# SparkFun_PWM_Shield.net
KiCad netlist of a schematic drawn in EAGLE
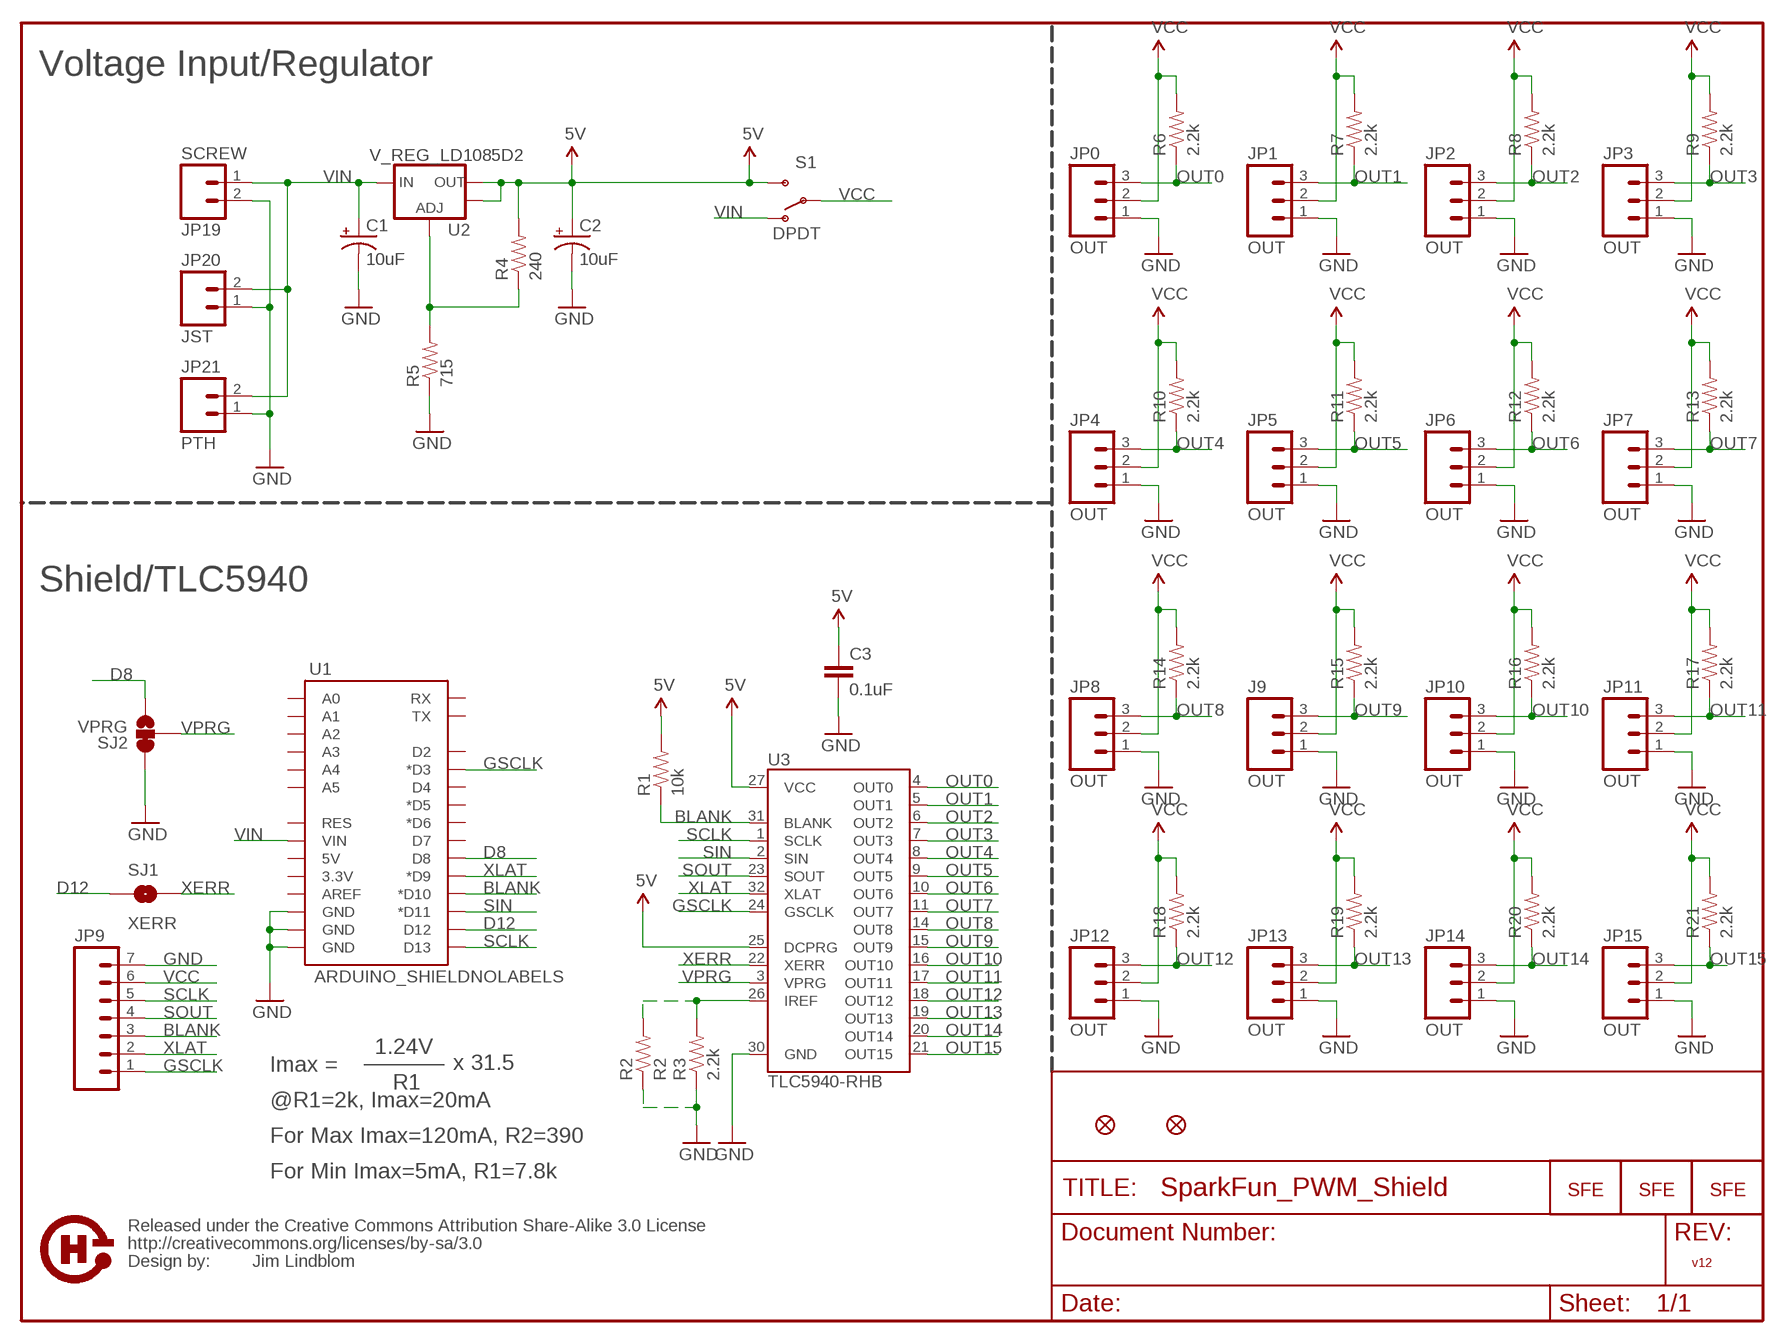
[diagram p0: schematic, sheet 1]

(export (version "E")
  (design (tool "Eeschema 10.0.6"))
  (components
    (comp (ref "C1")
      (value "10uF")
      (footprint "eagle-import:EIA3528")
      (libsource (lib "eagle-import") (part "CAP_POL3528"))
    )
    (comp (ref "C2")
      (value "10uF")
      (footprint "eagle-import:EIA3216")
      (libsource (lib "eagle-import") (part "CAP_POL1206"))
    )
    (comp (ref "C3")
      (value "0.1uF")
      (footprint "eagle-import:0402-CAP")
      (libsource (lib "eagle-import") (part "CAP0402-CAP"))
    )
    (comp (ref "J9")
      (value "OUT")
      (footprint "eagle-import:1X03")
      (libsource (lib "eagle-import") (part "M03PTH"))
    )
    (comp (ref "JP0")
      (value "OUT")
      (footprint "eagle-import:1X03")
      (libsource (lib "eagle-import") (part "M03PTH"))
    )
    (comp (ref "JP1")
      (value "OUT")
      (footprint "eagle-import:1X03")
      (libsource (lib "eagle-import") (part "M03PTH"))
    )
    (comp (ref "JP2")
      (value "OUT")
      (footprint "eagle-import:1X03")
      (libsource (lib "eagle-import") (part "M03PTH"))
    )
    (comp (ref "JP3")
      (value "OUT")
      (footprint "eagle-import:1X03")
      (libsource (lib "eagle-import") (part "M03PTH"))
    )
    (comp (ref "JP4")
      (value "OUT")
      (footprint "eagle-import:1X03")
      (libsource (lib "eagle-import") (part "M03PTH"))
    )
    (comp (ref "JP5")
      (value "OUT")
      (footprint "eagle-import:1X03")
      (libsource (lib "eagle-import") (part "M03PTH"))
    )
    (comp (ref "JP6")
      (value "OUT")
      (footprint "eagle-import:1X03")
      (libsource (lib "eagle-import") (part "M03PTH"))
    )
    (comp (ref "JP7")
      (value "OUT")
      (footprint "eagle-import:1X03")
      (libsource (lib "eagle-import") (part "M03PTH"))
    )
    (comp (ref "JP8")
      (value "OUT")
      (footprint "eagle-import:1X03")
      (libsource (lib "eagle-import") (part "M03PTH"))
    )
    (comp (ref "JP9")
      (value "M07")
      (footprint "eagle-import:1X07")
      (libsource (lib "eagle-import") (part "M07"))
    )
    (comp (ref "JP10")
      (value "OUT")
      (footprint "eagle-import:1X03")
      (libsource (lib "eagle-import") (part "M03PTH"))
    )
    (comp (ref "JP11")
      (value "OUT")
      (footprint "eagle-import:1X03")
      (libsource (lib "eagle-import") (part "M03PTH"))
    )
    (comp (ref "JP12")
      (value "OUT")
      (footprint "eagle-import:1X03")
      (libsource (lib "eagle-import") (part "M03PTH"))
    )
    (comp (ref "JP13")
      (value "OUT")
      (footprint "eagle-import:1X03")
      (libsource (lib "eagle-import") (part "M03PTH"))
    )
    (comp (ref "JP14")
      (value "OUT")
      (footprint "eagle-import:1X03")
      (libsource (lib "eagle-import") (part "M03PTH"))
    )
    (comp (ref "JP15")
      (value "OUT")
      (footprint "eagle-import:1X03")
      (libsource (lib "eagle-import") (part "M03PTH"))
    )
    (comp (ref "JP16")
      (value "LOGO-SFENEW")
      (footprint "eagle-import:SFE-NEW-WEBLOGO")
      (libsource (lib "eagle-import") (part "LOGO-SFENEW"))
    )
    (comp (ref "JP17")
      (value "LOGO-SFESK")
      (footprint "eagle-import:SFE-LOGO-FLAME")
      (libsource (lib "eagle-import") (part "LOGO-SFESK"))
    )
    (comp (ref "JP18")
      (value "LOGO-SFENW2")
      (footprint "eagle-import:SFE-NEW-WEB")
      (libsource (lib "eagle-import") (part "LOGO-SFENW2"))
    )
    (comp (ref "JP19")
      (value "SCREW")
      (footprint "eagle-import:SCREWTERMINAL-3.5MM-2-NS")
      (libsource (lib "eagle-import") (part "M023.5MM-NO_SILK"))
    )
    (comp (ref "JP20")
      (value "JST")
      (footprint "eagle-import:JST-2-PTH")
      (libsource (lib "eagle-import") (part "M02JST-PTH-2"))
    )
    (comp (ref "JP21")
      (value "PTH")
      (footprint "eagle-import:1X02")
      (libsource (lib "eagle-import") (part "M02PTH"))
    )
    (comp (ref "JP22")
      (value "FIDUCIAL1X2")
      (footprint "eagle-import:FIDUCIAL-1X2")
      (libsource (lib "eagle-import") (part "FIDUCIAL1X2"))
    )
    (comp (ref "JP23")
      (value "FIDUCIAL1X2")
      (footprint "eagle-import:FIDUCIAL-1X2")
      (libsource (lib "eagle-import") (part "FIDUCIAL1X2"))
    )
    (comp (ref "R1")
      (value "10k")
      (footprint "eagle-import:0402-RES")
      (libsource (lib "eagle-import") (part "RESISTOR0402-RES"))
    )
    (comp (ref "R2")
      (value "R2")
      (footprint "eagle-import:AXIAL-0.3")
      (libsource (lib "eagle-import") (part "RESISTORAXIAL-0.3"))
    )
    (comp (ref "R3")
      (value "2.2k")
      (footprint "eagle-import:0402-RES")
      (libsource (lib "eagle-import") (part "RESISTOR0402-RES"))
    )
    (comp (ref "R4")
      (value "240")
      (footprint "eagle-import:0402-RES")
      (libsource (lib "eagle-import") (part "RESISTOR0402-RES"))
    )
    (comp (ref "R5")
      (value "715")
      (footprint "eagle-import:0402-RES")
      (libsource (lib "eagle-import") (part "RESISTOR0402-RES"))
    )
    (comp (ref "R6")
      (value "2.2k")
      (footprint "eagle-import:0402-RES")
      (libsource (lib "eagle-import") (part "RESISTOR0402-RES"))
    )
    (comp (ref "R7")
      (value "2.2k")
      (footprint "eagle-import:0402-RES")
      (libsource (lib "eagle-import") (part "RESISTOR0402-RES"))
    )
    (comp (ref "R8")
      (value "2.2k")
      (footprint "eagle-import:0402-RES")
      (libsource (lib "eagle-import") (part "RESISTOR0402-RES"))
    )
    (comp (ref "R9")
      (value "2.2k")
      (footprint "eagle-import:0402-RES")
      (libsource (lib "eagle-import") (part "RESISTOR0402-RES"))
    )
    (comp (ref "R10")
      (value "2.2k")
      (footprint "eagle-import:0402-RES")
      (libsource (lib "eagle-import") (part "RESISTOR0402-RES"))
    )
    (comp (ref "R11")
      (value "2.2k")
      (footprint "eagle-import:0402-RES")
      (libsource (lib "eagle-import") (part "RESISTOR0402-RES"))
    )
    (comp (ref "R12")
      (value "2.2k")
      (footprint "eagle-import:0402-RES")
      (libsource (lib "eagle-import") (part "RESISTOR0402-RES"))
    )
    (comp (ref "R13")
      (value "2.2k")
      (footprint "eagle-import:0402-RES")
      (libsource (lib "eagle-import") (part "RESISTOR0402-RES"))
    )
    (comp (ref "R14")
      (value "2.2k")
      (footprint "eagle-import:0402-RES")
      (libsource (lib "eagle-import") (part "RESISTOR0402-RES"))
    )
    (comp (ref "R15")
      (value "2.2k")
      (footprint "eagle-import:0402-RES")
      (libsource (lib "eagle-import") (part "RESISTOR0402-RES"))
    )
    (comp (ref "R16")
      (value "2.2k")
      (footprint "eagle-import:0402-RES")
      (libsource (lib "eagle-import") (part "RESISTOR0402-RES"))
    )
    (comp (ref "R17")
      (value "2.2k")
      (footprint "eagle-import:0402-RES")
      (libsource (lib "eagle-import") (part "RESISTOR0402-RES"))
    )
    (comp (ref "R18")
      (value "2.2k")
      (footprint "eagle-import:0402-RES")
      (libsource (lib "eagle-import") (part "RESISTOR0402-RES"))
    )
    (comp (ref "R19")
      (value "2.2k")
      (footprint "eagle-import:0402-RES")
      (libsource (lib "eagle-import") (part "RESISTOR0402-RES"))
    )
    (comp (ref "R20")
      (value "2.2k")
      (footprint "eagle-import:0402-RES")
      (libsource (lib "eagle-import") (part "RESISTOR0402-RES"))
    )
    (comp (ref "R21")
      (value "2.2k")
      (footprint "eagle-import:0402-RES")
      (libsource (lib "eagle-import") (part "RESISTOR0402-RES"))
    )
    (comp (ref "S1")
      (value "DPDT")
      (footprint "eagle-import:AYZ0202")
      (libsource (lib "eagle-import") (part "SWITCH-SPSTSMD"))
    )
    (comp (ref "SJ1")
      (value "XERR")
      (footprint "eagle-import:SJ_2S-NO")
      (libsource (lib "eagle-import") (part "SOLDERJUMPERNO"))
    )
    (comp (ref "SJ2")
      (value "VPRG")
      (footprint "eagle-import:SJ_3")
      (libsource (lib "eagle-import") (part "SOLDERJUMPER_2WAYS"))
    )
    (comp (ref "U$1")
      (value "OSHW-LOGOORB")
      (footprint "eagle-import:OSHW-LOGO-GO")
      (libsource (lib "eagle-import") (part "OSHW-LOGOORB"))
    )
    (comp (ref "U$2")
      (value "CREATIVE_COMMONS")
      (footprint "eagle-import:CREATIVE_COMMONS")
      (libsource (lib "eagle-import") (part "CREATIVE_COMMONS"))
    )
    (comp (ref "U1")
      (value "ARDUINO_SHIELDNOLABELS")
      (footprint "eagle-import:DUEMILANOVE_SHIELD_NOLABELS")
      (libsource (lib "eagle-import") (part "ARDUINO_SHIELDNOLABELS"))
    )
    (comp (ref "U2")
      (value "V_REG_LD1085D2")
      (footprint "eagle-import:D2PACK_A")
      (libsource (lib "eagle-import") (part "V_REG_LD1085D2"))
    )
    (comp (ref "U3")
      (value "TLC5940-RHB")
      (footprint "eagle-import:QFN-32")
      (libsource (lib "eagle-import") (part "TLC5940-RHB"))
    )
  )
  (nets
    (net (code "1") (name "/BLANK") (class "Default")
      (node (ref "JP9") (pin "3") (pinfunction "3_3") (pintype "passive"))
      (node (ref "R1") (pin "1") (pinfunction "1_1") (pintype "passive"))
      (node (ref "U1") (pin "D10") (pinfunction "*D10_D10") (pintype "bidirectional"))
      (node (ref "U3") (pin "31") (pinfunction "BLANK_31") (pintype "bidirectional"))
    )
    (net (code "2") (name "/D8") (class "Default")
      (node (ref "SJ2") (pin "3") (pinfunction "3_3") (pintype "passive"))
      (node (ref "U1") (pin "D8") (pinfunction "D8_D8") (pintype "bidirectional"))
    )
    (net (code "3") (name "/D12") (class "Default")
      (node (ref "SJ1") (pin "1") (pinfunction "1_1") (pintype "passive"))
      (node (ref "U1") (pin "D12") (pinfunction "D12_D12") (pintype "bidirectional"))
    )
    (net (code "4") (name "/GSCLK") (class "Default")
      (node (ref "JP9") (pin "1") (pinfunction "1_1") (pintype "passive"))
      (node (ref "U1") (pin "D3") (pinfunction "*D3_D3") (pintype "bidirectional"))
      (node (ref "U3") (pin "24") (pinfunction "GSCLK_24") (pintype "bidirectional"))
    )
    (net (code "5") (name "/OUT0") (class "Default")
      (node (ref "JP0") (pin "3") (pinfunction "3_3") (pintype "passive"))
      (node (ref "R6") (pin "1") (pinfunction "1_1") (pintype "passive"))
      (node (ref "U3") (pin "4") (pinfunction "OUT0_4") (pintype "bidirectional"))
    )
    (net (code "6") (name "/OUT1") (class "Default")
      (node (ref "JP1") (pin "3") (pinfunction "3_3") (pintype "passive"))
      (node (ref "R7") (pin "1") (pinfunction "1_1") (pintype "passive"))
      (node (ref "U3") (pin "5") (pinfunction "OUT1_5") (pintype "bidirectional"))
    )
    (net (code "7") (name "/OUT2") (class "Default")
      (node (ref "JP2") (pin "3") (pinfunction "3_3") (pintype "passive"))
      (node (ref "R8") (pin "1") (pinfunction "1_1") (pintype "passive"))
      (node (ref "U3") (pin "6") (pinfunction "OUT2_6") (pintype "bidirectional"))
    )
    (net (code "8") (name "/OUT3") (class "Default")
      (node (ref "JP3") (pin "3") (pinfunction "3_3") (pintype "passive"))
      (node (ref "R9") (pin "1") (pinfunction "1_1") (pintype "passive"))
      (node (ref "U3") (pin "7") (pinfunction "OUT3_7") (pintype "bidirectional"))
    )
    (net (code "9") (name "/OUT4") (class "Default")
      (node (ref "JP4") (pin "3") (pinfunction "3_3") (pintype "passive"))
      (node (ref "R10") (pin "1") (pinfunction "1_1") (pintype "passive"))
      (node (ref "U3") (pin "8") (pinfunction "OUT4_8") (pintype "bidirectional"))
    )
    (net (code "10") (name "/OUT5") (class "Default")
      (node (ref "JP5") (pin "3") (pinfunction "3_3") (pintype "passive"))
      (node (ref "R11") (pin "1") (pinfunction "1_1") (pintype "passive"))
      (node (ref "U3") (pin "9") (pinfunction "OUT5_9") (pintype "bidirectional"))
    )
    (net (code "11") (name "/OUT6") (class "Default")
      (node (ref "JP6") (pin "3") (pinfunction "3_3") (pintype "passive"))
      (node (ref "R12") (pin "1") (pinfunction "1_1") (pintype "passive"))
      (node (ref "U3") (pin "10") (pinfunction "OUT6_10") (pintype "bidirectional"))
    )
    (net (code "12") (name "/OUT7") (class "Default")
      (node (ref "JP7") (pin "3") (pinfunction "3_3") (pintype "passive"))
      (node (ref "R13") (pin "1") (pinfunction "1_1") (pintype "passive"))
      (node (ref "U3") (pin "11") (pinfunction "OUT7_11") (pintype "bidirectional"))
    )
    (net (code "13") (name "/OUT8") (class "Default")
      (node (ref "JP8") (pin "3") (pinfunction "3_3") (pintype "passive"))
      (node (ref "R14") (pin "1") (pinfunction "1_1") (pintype "passive"))
      (node (ref "U3") (pin "14") (pinfunction "OUT8_14") (pintype "bidirectional"))
    )
    (net (code "14") (name "/OUT9") (class "Default")
      (node (ref "J9") (pin "3") (pinfunction "3_3") (pintype "passive"))
      (node (ref "R15") (pin "1") (pinfunction "1_1") (pintype "passive"))
      (node (ref "U3") (pin "15") (pinfunction "OUT9_15") (pintype "bidirectional"))
    )
    (net (code "15") (name "/OUT10") (class "Default")
      (node (ref "JP10") (pin "3") (pinfunction "3_3") (pintype "passive"))
      (node (ref "R16") (pin "1") (pinfunction "1_1") (pintype "passive"))
      (node (ref "U3") (pin "16") (pinfunction "OUT10_16") (pintype "bidirectional"))
    )
    (net (code "16") (name "/OUT11") (class "Default")
      (node (ref "JP11") (pin "3") (pinfunction "3_3") (pintype "passive"))
      (node (ref "R17") (pin "1") (pinfunction "1_1") (pintype "passive"))
      (node (ref "U3") (pin "17") (pinfunction "OUT11_17") (pintype "bidirectional"))
    )
    (net (code "17") (name "/OUT12") (class "Default")
      (node (ref "JP12") (pin "3") (pinfunction "3_3") (pintype "passive"))
      (node (ref "R18") (pin "1") (pinfunction "1_1") (pintype "passive"))
      (node (ref "U3") (pin "18") (pinfunction "OUT12_18") (pintype "bidirectional"))
    )
    (net (code "18") (name "/OUT13") (class "Default")
      (node (ref "JP13") (pin "3") (pinfunction "3_3") (pintype "passive"))
      (node (ref "R19") (pin "1") (pinfunction "1_1") (pintype "passive"))
      (node (ref "U3") (pin "19") (pinfunction "OUT13_19") (pintype "bidirectional"))
    )
    (net (code "19") (name "/OUT14") (class "Default")
      (node (ref "JP14") (pin "3") (pinfunction "3_3") (pintype "passive"))
      (node (ref "R20") (pin "1") (pinfunction "1_1") (pintype "passive"))
      (node (ref "U3") (pin "20") (pinfunction "OUT14_20") (pintype "bidirectional"))
    )
    (net (code "20") (name "/OUT15") (class "Default")
      (node (ref "JP15") (pin "3") (pinfunction "3_3") (pintype "passive"))
      (node (ref "R21") (pin "1") (pinfunction "1_1") (pintype "passive"))
      (node (ref "U3") (pin "21") (pinfunction "OUT15_21") (pintype "bidirectional"))
    )
    (net (code "21") (name "/SCLK") (class "Default")
      (node (ref "JP9") (pin "5") (pinfunction "5_5") (pintype "passive"))
      (node (ref "U1") (pin "D13") (pinfunction "D13_D13") (pintype "bidirectional"))
      (node (ref "U3") (pin "1") (pinfunction "SCLK_1") (pintype "bidirectional"))
    )
    (net (code "22") (name "/SIN") (class "Default")
      (node (ref "U1") (pin "D11") (pinfunction "*D11_D11") (pintype "bidirectional"))
      (node (ref "U3") (pin "2") (pinfunction "SIN_2") (pintype "bidirectional"))
    )
    (net (code "23") (name "/SOUT") (class "Default")
      (node (ref "JP9") (pin "4") (pinfunction "4_4") (pintype "passive"))
      (node (ref "U3") (pin "23") (pinfunction "SOUT_23") (pintype "bidirectional"))
    )
    (net (code "24") (name "/VIN") (class "Default")
      (node (ref "C1") (pin "A") (pinfunction "+_A") (pintype "passive"))
      (node (ref "JP19") (pin "1") (pinfunction "1_1") (pintype "passive"))
      (node (ref "JP20") (pin "2") (pinfunction "2_2") (pintype "passive"))
      (node (ref "JP21") (pin "2") (pinfunction "2_2") (pintype "passive"))
      (node (ref "S1") (pin "1") (pinfunction "O_1") (pintype "passive"))
      (node (ref "U1") (pin "VIN") (pinfunction "VIN_VIN") (pintype "bidirectional"))
      (node (ref "U2") (pin "3") (pinfunction "IN_3") (pintype "input"))
    )
    (net (code "25") (name "/VPRG") (class "Default")
      (node (ref "SJ2") (pin "2") (pinfunction "2_2") (pintype "passive"))
      (node (ref "U3") (pin "3") (pinfunction "VPRG_3") (pintype "bidirectional"))
    )
    (net (code "26") (name "/XERR") (class "Default")
      (node (ref "SJ1") (pin "2") (pinfunction "2_2") (pintype "passive"))
      (node (ref "U3") (pin "22") (pinfunction "XERR_22") (pintype "bidirectional"))
    )
    (net (code "27") (name "/XLAT") (class "Default")
      (node (ref "JP9") (pin "2") (pinfunction "2_2") (pintype "passive"))
      (node (ref "U1") (pin "D9") (pinfunction "*D9_D9") (pintype "bidirectional"))
      (node (ref "U3") (pin "32") (pinfunction "XLAT_32") (pintype "bidirectional"))
    )
    (net (code "28") (name "5V") (class "Default")
      (node (ref "C2") (pin "A") (pinfunction "+_A") (pintype "passive"))
      (node (ref "C3") (pin "1") (pinfunction "1_1") (pintype "passive"))
      (node (ref "R1") (pin "2") (pinfunction "2_2") (pintype "passive"))
      (node (ref "R4") (pin "2") (pinfunction "2_2") (pintype "passive"))
      (node (ref "S1") (pin "3") (pinfunction "S_3") (pintype "passive"))
      (node (ref "U2") (pin "2") (pinfunction "OUT_2") (pintype "output"))
      (node (ref "U2") (pin "TAB") (pinfunction "OUT_TAB") (pintype "output"))
      (node (ref "U3") (pin "25") (pinfunction "DCPRG_25") (pintype "bidirectional"))
      (node (ref "U3") (pin "27") (pinfunction "VCC_27") (pintype "bidirectional"))
    )
    (net (code "29") (name "GND") (class "Default")
      (node (ref "C1") (pin "C") (pinfunction "-_C") (pintype "passive"))
      (node (ref "C2") (pin "C") (pinfunction "-_C") (pintype "passive"))
      (node (ref "C3") (pin "2") (pinfunction "2_2") (pintype "passive"))
      (node (ref "J9") (pin "1") (pinfunction "1_1") (pintype "passive"))
      (node (ref "JP0") (pin "1") (pinfunction "1_1") (pintype "passive"))
      (node (ref "JP1") (pin "1") (pinfunction "1_1") (pintype "passive"))
      (node (ref "JP10") (pin "1") (pinfunction "1_1") (pintype "passive"))
      (node (ref "JP11") (pin "1") (pinfunction "1_1") (pintype "passive"))
      (node (ref "JP12") (pin "1") (pinfunction "1_1") (pintype "passive"))
      (node (ref "JP13") (pin "1") (pinfunction "1_1") (pintype "passive"))
      (node (ref "JP14") (pin "1") (pinfunction "1_1") (pintype "passive"))
      (node (ref "JP15") (pin "1") (pinfunction "1_1") (pintype "passive"))
      (node (ref "JP19") (pin "2") (pinfunction "2_2") (pintype "passive"))
      (node (ref "JP2") (pin "1") (pinfunction "1_1") (pintype "passive"))
      (node (ref "JP20") (pin "1") (pinfunction "1_1") (pintype "passive"))
      (node (ref "JP21") (pin "1") (pinfunction "1_1") (pintype "passive"))
      (node (ref "JP3") (pin "1") (pinfunction "1_1") (pintype "passive"))
      (node (ref "JP4") (pin "1") (pinfunction "1_1") (pintype "passive"))
      (node (ref "JP5") (pin "1") (pinfunction "1_1") (pintype "passive"))
      (node (ref "JP6") (pin "1") (pinfunction "1_1") (pintype "passive"))
      (node (ref "JP7") (pin "1") (pinfunction "1_1") (pintype "passive"))
      (node (ref "JP8") (pin "1") (pinfunction "1_1") (pintype "passive"))
      (node (ref "JP9") (pin "7") (pinfunction "7_7") (pintype "passive"))
      (node (ref "R2") (pin "P$1") (pinfunction "1_P$1") (pintype "passive"))
      (node (ref "R3") (pin "1") (pinfunction "1_1") (pintype "passive"))
      (node (ref "R5") (pin "1") (pinfunction "1_1") (pintype "passive"))
      (node (ref "SJ2") (pin "1") (pinfunction "1_1") (pintype "passive"))
      (node (ref "U1") (pin "GND@0") (pinfunction "GND_GND@0") (pintype "bidirectional"))
      (node (ref "U1") (pin "GND@1") (pinfunction "GND_GND@1") (pintype "bidirectional"))
      (node (ref "U1") (pin "GND@2") (pinfunction "GND_GND@2") (pintype "bidirectional"))
      (node (ref "U3") (pin "30") (pinfunction "GND_30") (pintype "bidirectional"))
    )
    (net (code "30") (name "Net-(R2-2)") (class "Default")
      (node (ref "R2") (pin "P$2") (pinfunction "2_P$2") (pintype "passive"))
      (node (ref "R3") (pin "2") (pinfunction "2_2") (pintype "passive"))
      (node (ref "U3") (pin "26") (pinfunction "IREF_26") (pintype "bidirectional"))
    )
    (net (code "31") (name "Net-(U2-ADJ)") (class "Default")
      (node (ref "R4") (pin "1") (pinfunction "1_1") (pintype "passive"))
      (node (ref "R5") (pin "2") (pinfunction "2_2") (pintype "passive"))
      (node (ref "U2") (pin "1") (pinfunction "ADJ_1") (pintype "input"))
    )
    (net (code "32") (name "VCC") (class "Default")
      (node (ref "J9") (pin "2") (pinfunction "2_2") (pintype "passive"))
      (node (ref "JP0") (pin "2") (pinfunction "2_2") (pintype "passive"))
      (node (ref "JP1") (pin "2") (pinfunction "2_2") (pintype "passive"))
      (node (ref "JP10") (pin "2") (pinfunction "2_2") (pintype "passive"))
      (node (ref "JP11") (pin "2") (pinfunction "2_2") (pintype "passive"))
      (node (ref "JP12") (pin "2") (pinfunction "2_2") (pintype "passive"))
      (node (ref "JP13") (pin "2") (pinfunction "2_2") (pintype "passive"))
      (node (ref "JP14") (pin "2") (pinfunction "2_2") (pintype "passive"))
      (node (ref "JP15") (pin "2") (pinfunction "2_2") (pintype "passive"))
      (node (ref "JP2") (pin "2") (pinfunction "2_2") (pintype "passive"))
      (node (ref "JP3") (pin "2") (pinfunction "2_2") (pintype "passive"))
      (node (ref "JP4") (pin "2") (pinfunction "2_2") (pintype "passive"))
      (node (ref "JP5") (pin "2") (pinfunction "2_2") (pintype "passive"))
      (node (ref "JP6") (pin "2") (pinfunction "2_2") (pintype "passive"))
      (node (ref "JP7") (pin "2") (pinfunction "2_2") (pintype "passive"))
      (node (ref "JP8") (pin "2") (pinfunction "2_2") (pintype "passive"))
      (node (ref "JP9") (pin "6") (pinfunction "6_6") (pintype "passive"))
      (node (ref "R10") (pin "2") (pinfunction "2_2") (pintype "passive"))
      (node (ref "R11") (pin "2") (pinfunction "2_2") (pintype "passive"))
      (node (ref "R12") (pin "2") (pinfunction "2_2") (pintype "passive"))
      (node (ref "R13") (pin "2") (pinfunction "2_2") (pintype "passive"))
      (node (ref "R14") (pin "2") (pinfunction "2_2") (pintype "passive"))
      (node (ref "R15") (pin "2") (pinfunction "2_2") (pintype "passive"))
      (node (ref "R16") (pin "2") (pinfunction "2_2") (pintype "passive"))
      (node (ref "R17") (pin "2") (pinfunction "2_2") (pintype "passive"))
      (node (ref "R18") (pin "2") (pinfunction "2_2") (pintype "passive"))
      (node (ref "R19") (pin "2") (pinfunction "2_2") (pintype "passive"))
      (node (ref "R20") (pin "2") (pinfunction "2_2") (pintype "passive"))
      (node (ref "R21") (pin "2") (pinfunction "2_2") (pintype "passive"))
      (node (ref "R6") (pin "2") (pinfunction "2_2") (pintype "passive"))
      (node (ref "R7") (pin "2") (pinfunction "2_2") (pintype "passive"))
      (node (ref "R8") (pin "2") (pinfunction "2_2") (pintype "passive"))
      (node (ref "R9") (pin "2") (pinfunction "2_2") (pintype "passive"))
      (node (ref "S1") (pin "2") (pinfunction "P_2") (pintype "passive"))
    )
    (net (code "33") (name "unconnected-(U1-*D5-PadD5)") (class "Default")
      (node (ref "U1") (pin "D5") (pinfunction "*D5_D5") (pintype "bidirectional"))
    )
    (net (code "34") (name "unconnected-(U1-*D6-PadD6)") (class "Default")
      (node (ref "U1") (pin "D6") (pinfunction "*D6_D6") (pintype "bidirectional"))
    )
    (net (code "35") (name "unconnected-(U1-Pad3.3V)") (class "Default")
      (node (ref "U1") (pin "3.3V") (pinfunction "3.3V_3.3V") (pintype "bidirectional"))
    )
    (net (code "36") (name "unconnected-(U1-Pad5V)") (class "Default")
      (node (ref "U1") (pin "5V") (pinfunction "5V_5V") (pintype "bidirectional"))
    )
    (net (code "37") (name "unconnected-(U1-PadA0)") (class "Default")
      (node (ref "U1") (pin "A0") (pinfunction "A0_A0") (pintype "bidirectional"))
    )
    (net (code "38") (name "unconnected-(U1-PadA1)") (class "Default")
      (node (ref "U1") (pin "A1") (pinfunction "A1_A1") (pintype "bidirectional"))
    )
    (net (code "39") (name "unconnected-(U1-PadA2)") (class "Default")
      (node (ref "U1") (pin "A2") (pinfunction "A2_A2") (pintype "bidirectional"))
    )
    (net (code "40") (name "unconnected-(U1-PadA3)") (class "Default")
      (node (ref "U1") (pin "A3") (pinfunction "A3_A3") (pintype "bidirectional"))
    )
    (net (code "41") (name "unconnected-(U1-PadA4)") (class "Default")
      (node (ref "U1") (pin "A4") (pinfunction "A4_A4") (pintype "bidirectional"))
    )
    (net (code "42") (name "unconnected-(U1-PadA5)") (class "Default")
      (node (ref "U1") (pin "A5") (pinfunction "A5_A5") (pintype "bidirectional"))
    )
    (net (code "43") (name "unconnected-(U1-PadAREF)") (class "Default")
      (node (ref "U1") (pin "AREF") (pinfunction "AREF_AREF") (pintype "bidirectional"))
    )
    (net (code "44") (name "unconnected-(U1-PadD2)") (class "Default")
      (node (ref "U1") (pin "D2") (pinfunction "D2_D2") (pintype "bidirectional"))
    )
    (net (code "45") (name "unconnected-(U1-PadD4)") (class "Default")
      (node (ref "U1") (pin "D4") (pinfunction "D4_D4") (pintype "bidirectional"))
    )
    (net (code "46") (name "unconnected-(U1-PadD7)") (class "Default")
      (node (ref "U1") (pin "D7") (pinfunction "D7_D7") (pintype "bidirectional"))
    )
    (net (code "47") (name "unconnected-(U1-PadRES)") (class "Default")
      (node (ref "U1") (pin "RES") (pinfunction "RES_RES") (pintype "bidirectional"))
    )
    (net (code "48") (name "unconnected-(U1-PadRX)") (class "Default")
      (node (ref "U1") (pin "RX") (pinfunction "RX_RX") (pintype "bidirectional"))
    )
    (net (code "49") (name "unconnected-(U1-PadTX)") (class "Default")
      (node (ref "U1") (pin "TX") (pinfunction "TX_TX") (pintype "bidirectional"))
    )
  )
)
